# goodthopter12.net
KiCad netlist of a schematic drawn in EAGLE
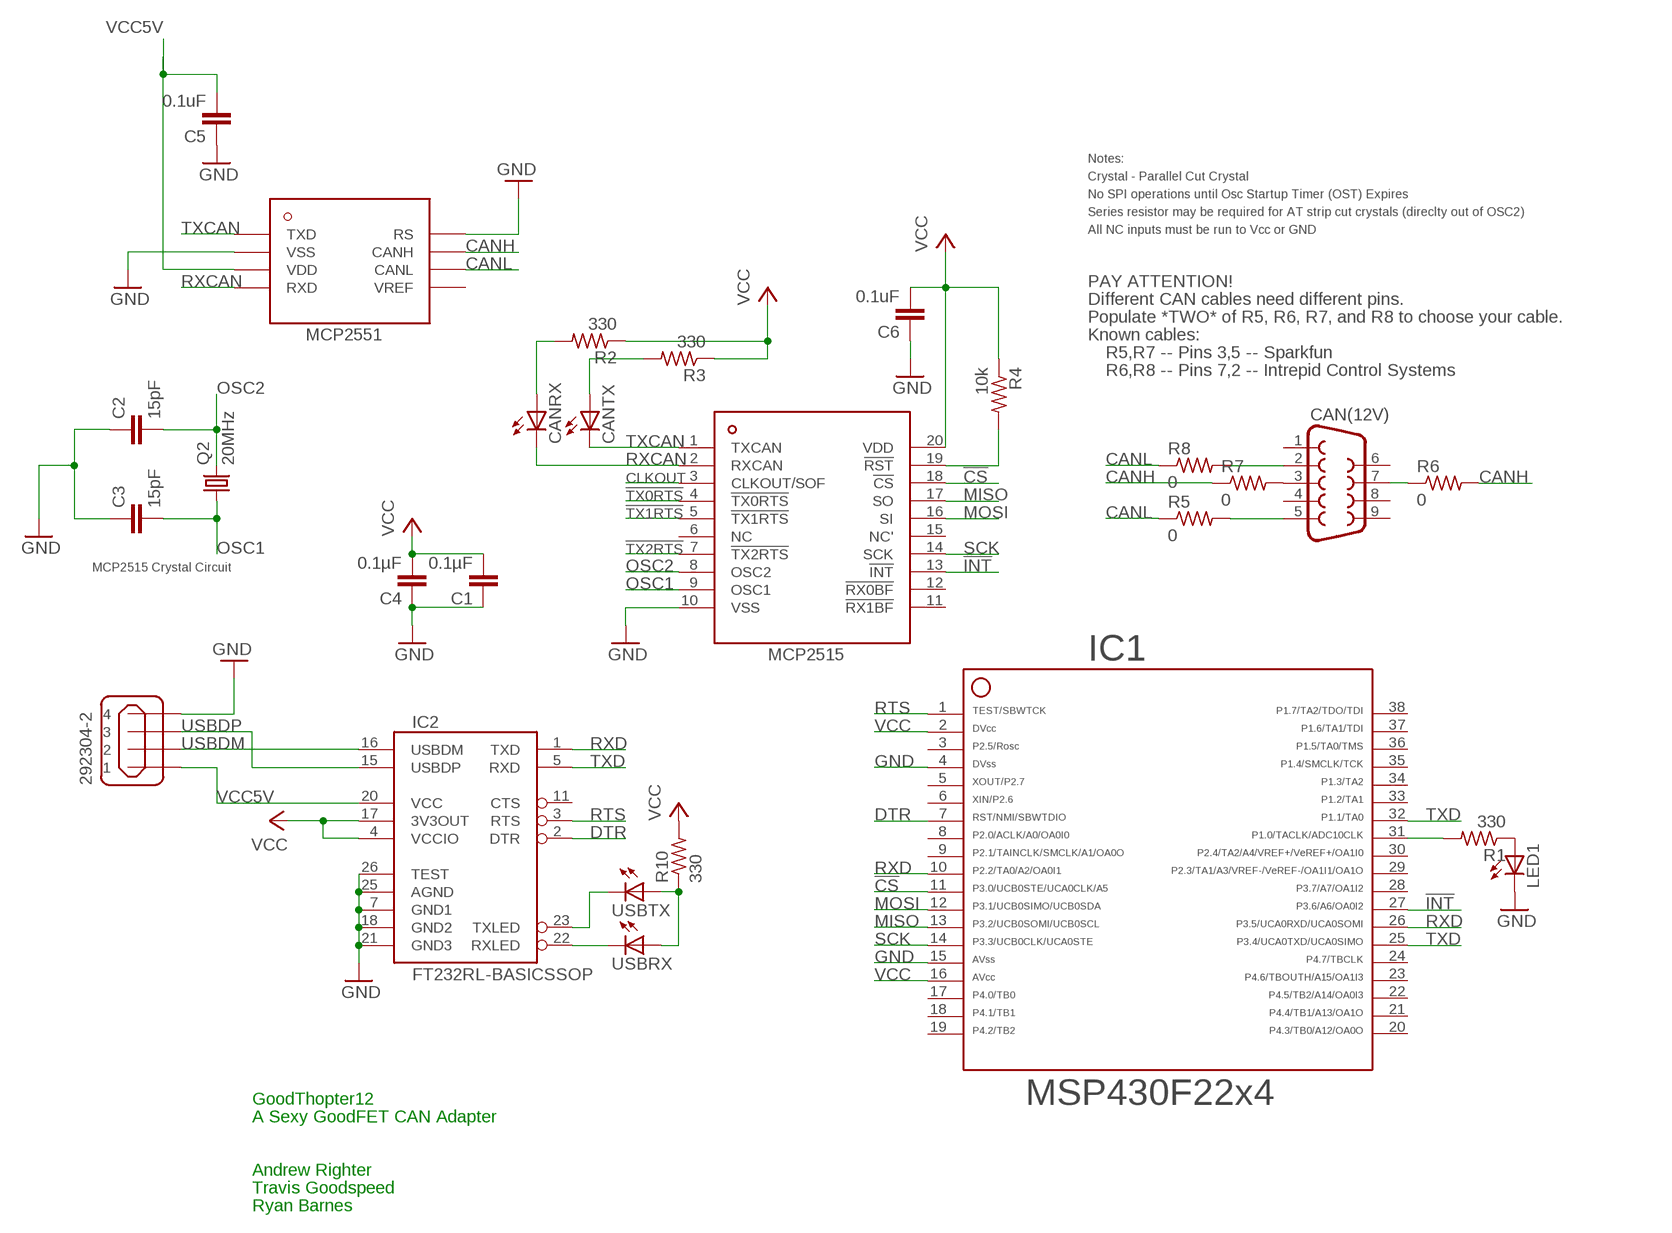
[diagram p0: schematic, sheet 1]

(export (version "E")
  (design (tool "Eeschema 10.0.6"))
  (components
    (comp (ref "292304-2")
      (value "MINI-USB_4P-292304-2")
      (footprint "eagle-import:85-32004-10X")
      (libsource (lib "eagle-import") (part "MINI-USB_4P-292304-2"))
    )
    (comp (ref "C1")
      (value "0.1µF")
      (footprint "eagle-import:C0603")
      (libsource (lib "eagle-import") (part "C-EUC0603"))
    )
    (comp (ref "C2")
      (value "15pF")
      (footprint "eagle-import:C0603")
      (libsource (lib "eagle-import") (part "C-EUC0603"))
    )
    (comp (ref "C3")
      (value "15pF")
      (footprint "eagle-import:C0603")
      (libsource (lib "eagle-import") (part "C-EUC0603"))
    )
    (comp (ref "C4")
      (value "0.1µF")
      (footprint "eagle-import:C0603")
      (libsource (lib "eagle-import") (part "C-EUC0603"))
    )
    (comp (ref "C5")
      (value "0.1uF")
      (footprint "eagle-import:C0603")
      (libsource (lib "eagle-import") (part "C-EUC0603"))
    )
    (comp (ref "C6")
      (value "0.1uF")
      (footprint "eagle-import:C0603")
      (libsource (lib "eagle-import") (part "C-EUC0603"))
    )
    (comp (ref "CAN(12V)")
      (value "DB9MALE")
      (footprint "eagle-import:DB9_MALE")
      (libsource (lib "eagle-import") (part "DB9MALE"))
    )
    (comp (ref "CANRX")
      (value "LEDCHIP-LED0603")
      (footprint "eagle-import:CHIP-LED0603")
      (libsource (lib "eagle-import") (part "LEDCHIP-LED0603"))
    )
    (comp (ref "CANTX")
      (value "LEDCHIP-LED0603")
      (footprint "eagle-import:CHIP-LED0603")
      (libsource (lib "eagle-import") (part "LEDCHIP-LED0603"))
    )
    (comp (ref "IC1")
      (value "F22X4---DA38")
      (footprint "eagle-import:DA38")
      (libsource (lib "eagle-import") (part "F22X4---DA38"))
    )
    (comp (ref "IC2")
      (value "FT232RL-BASICSSOP")
      (footprint "eagle-import:SSOP28DB")
      (libsource (lib "eagle-import") (part "FT232RL-BASICSSOP"))
    )
    (comp (ref "LED1")
      (value "LEDCHIP-LED0603")
      (footprint "eagle-import:CHIP-LED0603")
      (libsource (lib "eagle-import") (part "LEDCHIP-LED0603"))
    )
    (comp (ref "Q2")
      (value "20MHz")
      (footprint "eagle-import:HC49UP")
      (libsource (lib "eagle-import") (part "CRYSTALHC49UP"))
    )
    (comp (ref "R1")
      (value "330")
      (footprint "eagle-import:R0603")
      (libsource (lib "eagle-import") (part "R-US_R0603"))
    )
    (comp (ref "R2")
      (value "330")
      (footprint "eagle-import:R0603")
      (libsource (lib "eagle-import") (part "R-US_R0603"))
    )
    (comp (ref "R3")
      (value "330")
      (footprint "eagle-import:R0603")
      (libsource (lib "eagle-import") (part "R-US_R0603"))
    )
    (comp (ref "R4")
      (value "10k")
      (footprint "eagle-import:R0603")
      (libsource (lib "eagle-import") (part "R-US_R0603"))
    )
    (comp (ref "R5")
      (value "0")
      (footprint "eagle-import:R0603")
      (libsource (lib "eagle-import") (part "R-US_R0603"))
    )
    (comp (ref "R6")
      (value "0")
      (footprint "eagle-import:R0603")
      (libsource (lib "eagle-import") (part "R-US_R0603"))
    )
    (comp (ref "R7")
      (value "0")
      (footprint "eagle-import:R0603")
      (libsource (lib "eagle-import") (part "R-US_R0603"))
    )
    (comp (ref "R8")
      (value "0")
      (footprint "eagle-import:R0603")
      (libsource (lib "eagle-import") (part "R-US_R0603"))
    )
    (comp (ref "R10")
      (value "330")
      (footprint "eagle-import:R0603")
      (libsource (lib "eagle-import") (part "R-US_R0603"))
    )
    (comp (ref "U$1")
      (value "MCP2515")
      (footprint "eagle-import:TSSOP20")
      (libsource (lib "eagle-import") (part "MCP2515"))
    )
    (comp (ref "U$2")
      (value "MCP2551")
      (footprint "eagle-import:SOIC-8")
      (libsource (lib "eagle-import") (part "MCP2551"))
    )
    (comp (ref "USBRX")
      (value "LEDCHIP-LED0603")
      (footprint "eagle-import:CHIP-LED0603")
      (libsource (lib "eagle-import") (part "LEDCHIP-LED0603"))
    )
    (comp (ref "USBTX")
      (value "LEDCHIP-LED0603")
      (footprint "eagle-import:CHIP-LED0603")
      (libsource (lib "eagle-import") (part "LEDCHIP-LED0603"))
    )
  )
  (nets
    (net (code "1") (name "/CANH") (class "Default")
      (node (ref "R6") (pin "2") (pinfunction "2_2") (pintype "passive"))
      (node (ref "R7") (pin "1") (pinfunction "1_1") (pintype "passive"))
      (node (ref "U$2") (pin "CANH") (pinfunction "CANH_CANH") (pintype "bidirectional"))
    )
    (net (code "2") (name "/CANL") (class "Default")
      (node (ref "R5") (pin "1") (pinfunction "1_1") (pintype "passive"))
      (node (ref "R8") (pin "1") (pinfunction "1_1") (pintype "passive"))
      (node (ref "U$2") (pin "CANL") (pinfunction "CANL_CANL") (pintype "bidirectional"))
    )
    (net (code "3") (name "/CLKOUT") (class "Default")
      (node (ref "U$1") (pin "3") (pinfunction "CLKOUT/SOF_3") (pintype "bidirectional"))
    )
    (net (code "4") (name "/DTR") (class "Default")
      (node (ref "IC1") (pin "7") (pinfunction "7_7") (pintype "bidirectional"))
      (node (ref "IC2") (pin "2") (pinfunction "DTR_2") (pintype "bidirectional"))
    )
    (net (code "5") (name "/MISO") (class "Default")
      (node (ref "IC1") (pin "13") (pinfunction "13_13") (pintype "bidirectional"))
      (node (ref "U$1") (pin "17") (pinfunction "SO_17") (pintype "bidirectional"))
    )
    (net (code "6") (name "/MOSI") (class "Default")
      (node (ref "IC1") (pin "12") (pinfunction "12_12") (pintype "bidirectional"))
      (node (ref "U$1") (pin "16") (pinfunction "SI_16") (pintype "bidirectional"))
    )
    (net (code "7") (name "/OSC1") (class "Default")
      (node (ref "C3") (pin "2") (pinfunction "2_2") (pintype "passive"))
      (node (ref "Q2") (pin "1") (pinfunction "1_1") (pintype "passive"))
      (node (ref "U$1") (pin "9") (pinfunction "OSC1_9") (pintype "bidirectional"))
    )
    (net (code "8") (name "/OSC2") (class "Default")
      (node (ref "C2") (pin "2") (pinfunction "2_2") (pintype "passive"))
      (node (ref "Q2") (pin "2") (pinfunction "2_2") (pintype "passive"))
      (node (ref "U$1") (pin "8") (pinfunction "OSC2_8") (pintype "bidirectional"))
    )
    (net (code "9") (name "/RTS") (class "Default")
      (node (ref "IC1") (pin "1") (pinfunction "1_1") (pintype "input"))
      (node (ref "IC2") (pin "3") (pinfunction "RTS_3") (pintype "bidirectional"))
    )
    (net (code "10") (name "/RXCAN") (class "Default")
      (node (ref "CANRX") (pin "C") (pinfunction "C_C") (pintype "passive"))
      (node (ref "U$1") (pin "2") (pinfunction "RXCAN_2") (pintype "bidirectional"))
      (node (ref "U$2") (pin "RXD") (pinfunction "RXD_RXD") (pintype "bidirectional"))
    )
    (net (code "11") (name "/RXD") (class "Default")
      (node (ref "IC1") (pin "10") (pinfunction "10_10") (pintype "bidirectional"))
      (node (ref "IC1") (pin "26") (pinfunction "26_26") (pintype "bidirectional"))
      (node (ref "IC2") (pin "1") (pinfunction "TXD_1") (pintype "output"))
    )
    (net (code "12") (name "/SCK") (class "Default")
      (node (ref "IC1") (pin "14") (pinfunction "14_14") (pintype "bidirectional"))
      (node (ref "U$1") (pin "14") (pinfunction "SCK_14") (pintype "bidirectional"))
    )
    (net (code "13") (name "/TXCAN") (class "Default")
      (node (ref "CANTX") (pin "C") (pinfunction "C_C") (pintype "passive"))
      (node (ref "U$1") (pin "1") (pinfunction "TXCAN_1") (pintype "bidirectional"))
      (node (ref "U$2") (pin "TXD") (pinfunction "TXD_TXD") (pintype "bidirectional"))
    )
    (net (code "14") (name "/TXD") (class "Default")
      (node (ref "IC1") (pin "25") (pinfunction "25_25") (pintype "bidirectional"))
      (node (ref "IC1") (pin "32") (pinfunction "32_32") (pintype "bidirectional"))
      (node (ref "IC2") (pin "5") (pinfunction "RXD_5") (pintype "input"))
    )
    (net (code "15") (name "/USBDM") (class "Default")
      (node (ref "292304-2") (pin "2") (pinfunction "2_2") (pintype "passive"))
      (node (ref "IC2") (pin "16") (pinfunction "USBDM_16") (pintype "bidirectional"))
    )
    (net (code "16") (name "/USBDP") (class "Default")
      (node (ref "292304-2") (pin "3") (pinfunction "3_3") (pintype "passive"))
      (node (ref "IC2") (pin "15") (pinfunction "USBDP_15") (pintype "bidirectional"))
    )
    (net (code "17") (name "/VCC5V") (class "Default")
      (node (ref "292304-2") (pin "1") (pinfunction "1_1") (pintype "passive"))
      (node (ref "C5") (pin "2") (pinfunction "2_2") (pintype "passive"))
      (node (ref "IC2") (pin "20") (pinfunction "VCC_20") (pintype "power_in"))
      (node (ref "U$2") (pin "VDD") (pinfunction "VDD_VDD") (pintype "bidirectional"))
    )
    (net (code "18") (name "/~{CS}") (class "Default")
      (node (ref "IC1") (pin "11") (pinfunction "11_11") (pintype "bidirectional"))
      (node (ref "U$1") (pin "18") (pinfunction "~{CS}_18") (pintype "bidirectional"))
    )
    (net (code "19") (name "/~{INT}") (class "Default")
      (node (ref "IC1") (pin "27") (pinfunction "27_27") (pintype "bidirectional"))
      (node (ref "U$1") (pin "13") (pinfunction "~{INT}_13") (pintype "bidirectional"))
    )
    (net (code "20") (name "/~{TX0RTS}") (class "Default")
      (node (ref "U$1") (pin "4") (pinfunction "~{TX0RTS}_4") (pintype "bidirectional"))
    )
    (net (code "21") (name "/~{TX1RTS}") (class "Default")
      (node (ref "U$1") (pin "5") (pinfunction "~{TX1RTS}_5") (pintype "bidirectional"))
    )
    (net (code "22") (name "/~{TX2RTS}") (class "Default")
      (node (ref "U$1") (pin "7") (pinfunction "~{TX2RTS}_7") (pintype "bidirectional"))
    )
    (net (code "23") (name "GND") (class "Default")
      (node (ref "292304-2") (pin "4") (pinfunction "4_4") (pintype "passive"))
      (node (ref "C1") (pin "1") (pinfunction "1_1") (pintype "passive"))
      (node (ref "C2") (pin "1") (pinfunction "1_1") (pintype "passive"))
      (node (ref "C3") (pin "1") (pinfunction "1_1") (pintype "passive"))
      (node (ref "C4") (pin "1") (pinfunction "1_1") (pintype "passive"))
      (node (ref "C5") (pin "1") (pinfunction "1_1") (pintype "passive"))
      (node (ref "C6") (pin "1") (pinfunction "1_1") (pintype "passive"))
      (node (ref "IC1") (pin "15") (pinfunction "15_15") (pintype "power_in"))
      (node (ref "IC1") (pin "4") (pinfunction "4_4") (pintype "power_in"))
      (node (ref "IC2") (pin "18") (pinfunction "GND2_18") (pintype "power_in"))
      (node (ref "IC2") (pin "21") (pinfunction "GND3_21") (pintype "power_in"))
      (node (ref "IC2") (pin "25") (pinfunction "AGND_25") (pintype "power_in"))
      (node (ref "IC2") (pin "26") (pinfunction "TEST_26") (pintype "input"))
      (node (ref "IC2") (pin "7") (pinfunction "GND1_7") (pintype "power_in"))
      (node (ref "LED1") (pin "C") (pinfunction "C_C") (pintype "passive"))
      (node (ref "U$1") (pin "10") (pinfunction "VSS_10") (pintype "bidirectional"))
      (node (ref "U$2") (pin "RS") (pinfunction "RS_RS") (pintype "bidirectional"))
      (node (ref "U$2") (pin "VSS") (pinfunction "VSS_VSS") (pintype "bidirectional"))
    )
    (net (code "24") (name "Net-(CAN(12V)-Pad2)") (class "Default")
      (node (ref "CAN(12V)") (pin "2") (pinfunction "2_2") (pintype "passive"))
      (node (ref "R8") (pin "2") (pinfunction "2_2") (pintype "passive"))
    )
    (net (code "25") (name "Net-(CAN(12V)-Pad3)") (class "Default")
      (node (ref "CAN(12V)") (pin "3") (pinfunction "3_3") (pintype "passive"))
      (node (ref "R7") (pin "2") (pinfunction "2_2") (pintype "passive"))
    )
    (net (code "26") (name "Net-(CAN(12V)-Pad5)") (class "Default")
      (node (ref "CAN(12V)") (pin "5") (pinfunction "5_5") (pintype "passive"))
      (node (ref "R5") (pin "2") (pinfunction "2_2") (pintype "passive"))
    )
    (net (code "27") (name "Net-(CAN(12V)-Pad7)") (class "Default")
      (node (ref "CAN(12V)") (pin "7") (pinfunction "7_7") (pintype "passive"))
      (node (ref "R6") (pin "1") (pinfunction "1_1") (pintype "passive"))
    )
    (net (code "28") (name "Net-(CANRX-PadA)") (class "Default")
      (node (ref "CANRX") (pin "A") (pinfunction "A_A") (pintype "passive"))
      (node (ref "R2") (pin "2") (pinfunction "2_2") (pintype "passive"))
    )
    (net (code "29") (name "Net-(CANTX-PadA)") (class "Default")
      (node (ref "CANTX") (pin "A") (pinfunction "A_A") (pintype "passive"))
      (node (ref "R3") (pin "2") (pinfunction "2_2") (pintype "passive"))
    )
    (net (code "30") (name "Net-(IC1-Pad31)") (class "Default")
      (node (ref "IC1") (pin "31") (pinfunction "31_31") (pintype "bidirectional"))
      (node (ref "R1") (pin "2") (pinfunction "2_2") (pintype "passive"))
    )
    (net (code "31") (name "Net-(IC2-RXLED)") (class "Default")
      (node (ref "IC2") (pin "22") (pinfunction "RXLED_22") (pintype "bidirectional"))
      (node (ref "USBRX") (pin "C") (pinfunction "C_C") (pintype "passive"))
    )
    (net (code "32") (name "Net-(IC2-TXLED)") (class "Default")
      (node (ref "IC2") (pin "23") (pinfunction "TXLED_23") (pintype "bidirectional"))
      (node (ref "USBTX") (pin "C") (pinfunction "C_C") (pintype "passive"))
    )
    (net (code "33") (name "Net-(LED1-PadA)") (class "Default")
      (node (ref "LED1") (pin "A") (pinfunction "A_A") (pintype "passive"))
      (node (ref "R1") (pin "1") (pinfunction "1_1") (pintype "passive"))
    )
    (net (code "34") (name "Net-(R10-Pad1)") (class "Default")
      (node (ref "R10") (pin "1") (pinfunction "1_1") (pintype "passive"))
      (node (ref "USBRX") (pin "A") (pinfunction "A_A") (pintype "passive"))
      (node (ref "USBTX") (pin "A") (pinfunction "A_A") (pintype "passive"))
    )
    (net (code "35") (name "Net-(U$1-~{RST})") (class "Default")
      (node (ref "R4") (pin "2") (pinfunction "2_2") (pintype "passive"))
      (node (ref "U$1") (pin "19") (pinfunction "~{RST}_19") (pintype "bidirectional"))
    )
    (net (code "36") (name "VCC") (class "Default")
      (node (ref "C1") (pin "2") (pinfunction "2_2") (pintype "passive"))
      (node (ref "C4") (pin "2") (pinfunction "2_2") (pintype "passive"))
      (node (ref "C6") (pin "2") (pinfunction "2_2") (pintype "passive"))
      (node (ref "IC1") (pin "16") (pinfunction "16_16") (pintype "power_in"))
      (node (ref "IC1") (pin "2") (pinfunction "2_2") (pintype "power_in"))
      (node (ref "IC2") (pin "17") (pinfunction "3V3OUT_17") (pintype "output"))
      (node (ref "IC2") (pin "4") (pinfunction "VCCIO_4") (pintype "power_in"))
      (node (ref "R10") (pin "2") (pinfunction "2_2") (pintype "passive"))
      (node (ref "R2") (pin "1") (pinfunction "1_1") (pintype "passive"))
      (node (ref "R3") (pin "1") (pinfunction "1_1") (pintype "passive"))
      (node (ref "R4") (pin "1") (pinfunction "1_1") (pintype "passive"))
      (node (ref "U$1") (pin "20") (pinfunction "VDD_20") (pintype "bidirectional"))
    )
    (net (code "37") (name "unconnected-(CAN(12V)-Pad1)") (class "Default")
      (node (ref "CAN(12V)") (pin "1") (pinfunction "1_1") (pintype "passive"))
    )
    (net (code "38") (name "unconnected-(CAN(12V)-Pad4)") (class "Default")
      (node (ref "CAN(12V)") (pin "4") (pinfunction "4_4") (pintype "passive"))
    )
    (net (code "39") (name "unconnected-(CAN(12V)-Pad6)") (class "Default")
      (node (ref "CAN(12V)") (pin "6") (pinfunction "6_6") (pintype "passive"))
    )
    (net (code "40") (name "unconnected-(CAN(12V)-Pad8)") (class "Default")
      (node (ref "CAN(12V)") (pin "8") (pinfunction "8_8") (pintype "passive"))
    )
    (net (code "41") (name "unconnected-(CAN(12V)-Pad9)") (class "Default")
      (node (ref "CAN(12V)") (pin "9") (pinfunction "9_9") (pintype "passive"))
    )
    (net (code "42") (name "unconnected-(IC1-Pad3)") (class "Default")
      (node (ref "IC1") (pin "3") (pinfunction "3_3") (pintype "bidirectional"))
    )
    (net (code "43") (name "unconnected-(IC1-Pad5)") (class "Default")
      (node (ref "IC1") (pin "5") (pinfunction "5_5") (pintype "bidirectional"))
    )
    (net (code "44") (name "unconnected-(IC1-Pad6)") (class "Default")
      (node (ref "IC1") (pin "6") (pinfunction "6_6") (pintype "bidirectional"))
    )
    (net (code "45") (name "unconnected-(IC1-Pad8)") (class "Default")
      (node (ref "IC1") (pin "8") (pinfunction "8_8") (pintype "bidirectional"))
    )
    (net (code "46") (name "unconnected-(IC1-Pad9)") (class "Default")
      (node (ref "IC1") (pin "9") (pinfunction "9_9") (pintype "bidirectional"))
    )
    (net (code "47") (name "unconnected-(IC1-Pad17)") (class "Default")
      (node (ref "IC1") (pin "17") (pinfunction "17_17") (pintype "bidirectional"))
    )
    (net (code "48") (name "unconnected-(IC1-Pad18)") (class "Default")
      (node (ref "IC1") (pin "18") (pinfunction "18_18") (pintype "bidirectional"))
    )
    (net (code "49") (name "unconnected-(IC1-Pad19)") (class "Default")
      (node (ref "IC1") (pin "19") (pinfunction "19_19") (pintype "bidirectional"))
    )
    (net (code "50") (name "unconnected-(IC1-Pad20)") (class "Default")
      (node (ref "IC1") (pin "20") (pinfunction "20_20") (pintype "bidirectional"))
    )
    (net (code "51") (name "unconnected-(IC1-Pad21)") (class "Default")
      (node (ref "IC1") (pin "21") (pinfunction "21_21") (pintype "bidirectional"))
    )
    (net (code "52") (name "unconnected-(IC1-Pad22)") (class "Default")
      (node (ref "IC1") (pin "22") (pinfunction "22_22") (pintype "bidirectional"))
    )
    (net (code "53") (name "unconnected-(IC1-Pad23)") (class "Default")
      (node (ref "IC1") (pin "23") (pinfunction "23_23") (pintype "bidirectional"))
    )
    (net (code "54") (name "unconnected-(IC1-Pad24)") (class "Default")
      (node (ref "IC1") (pin "24") (pinfunction "24_24") (pintype "bidirectional"))
    )
    (net (code "55") (name "unconnected-(IC1-Pad28)") (class "Default")
      (node (ref "IC1") (pin "28") (pinfunction "28_28") (pintype "bidirectional"))
    )
    (net (code "56") (name "unconnected-(IC1-Pad29)") (class "Default")
      (node (ref "IC1") (pin "29") (pinfunction "29_29") (pintype "bidirectional"))
    )
    (net (code "57") (name "unconnected-(IC1-Pad30)") (class "Default")
      (node (ref "IC1") (pin "30") (pinfunction "30_30") (pintype "bidirectional"))
    )
    (net (code "58") (name "unconnected-(IC1-Pad33)") (class "Default")
      (node (ref "IC1") (pin "33") (pinfunction "33_33") (pintype "bidirectional"))
    )
    (net (code "59") (name "unconnected-(IC1-Pad34)") (class "Default")
      (node (ref "IC1") (pin "34") (pinfunction "34_34") (pintype "bidirectional"))
    )
    (net (code "60") (name "unconnected-(IC1-Pad35)") (class "Default")
      (node (ref "IC1") (pin "35") (pinfunction "35_35") (pintype "bidirectional"))
    )
    (net (code "61") (name "unconnected-(IC1-Pad36)") (class "Default")
      (node (ref "IC1") (pin "36") (pinfunction "36_36") (pintype "bidirectional"))
    )
    (net (code "62") (name "unconnected-(IC1-Pad37)") (class "Default")
      (node (ref "IC1") (pin "37") (pinfunction "37_37") (pintype "bidirectional"))
    )
    (net (code "63") (name "unconnected-(IC1-Pad38)") (class "Default")
      (node (ref "IC1") (pin "38") (pinfunction "38_38") (pintype "bidirectional"))
    )
    (net (code "64") (name "unconnected-(IC2-CTS-Pad11)") (class "Default")
      (node (ref "IC2") (pin "11") (pinfunction "CTS_11") (pintype "bidirectional"))
    )
    (net (code "65") (name "unconnected-(U$1-NC'-Pad15)") (class "Default")
      (node (ref "U$1") (pin "15") (pinfunction "NC'_15") (pintype "bidirectional"))
    )
    (net (code "66") (name "unconnected-(U$1-NC-Pad6)") (class "Default")
      (node (ref "U$1") (pin "6") (pinfunction "NC_6") (pintype "bidirectional"))
    )
    (net (code "67") (name "unconnected-(U$1-~{RX0BF}-Pad12)") (class "Default")
      (node (ref "U$1") (pin "12") (pinfunction "~{RX0BF}_12") (pintype "bidirectional"))
    )
    (net (code "68") (name "unconnected-(U$1-~{RX1BF}-Pad11)") (class "Default")
      (node (ref "U$1") (pin "11") (pinfunction "~{RX1BF}_11") (pintype "bidirectional"))
    )
    (net (code "69") (name "unconnected-(U$2-PadVREF)") (class "Default")
      (node (ref "U$2") (pin "VREF") (pinfunction "VREF_VREF") (pintype "bidirectional"))
    )
  )
)
